# EP2C5T144C8.net
KiCad netlist of a schematic drawn in Altium Designer
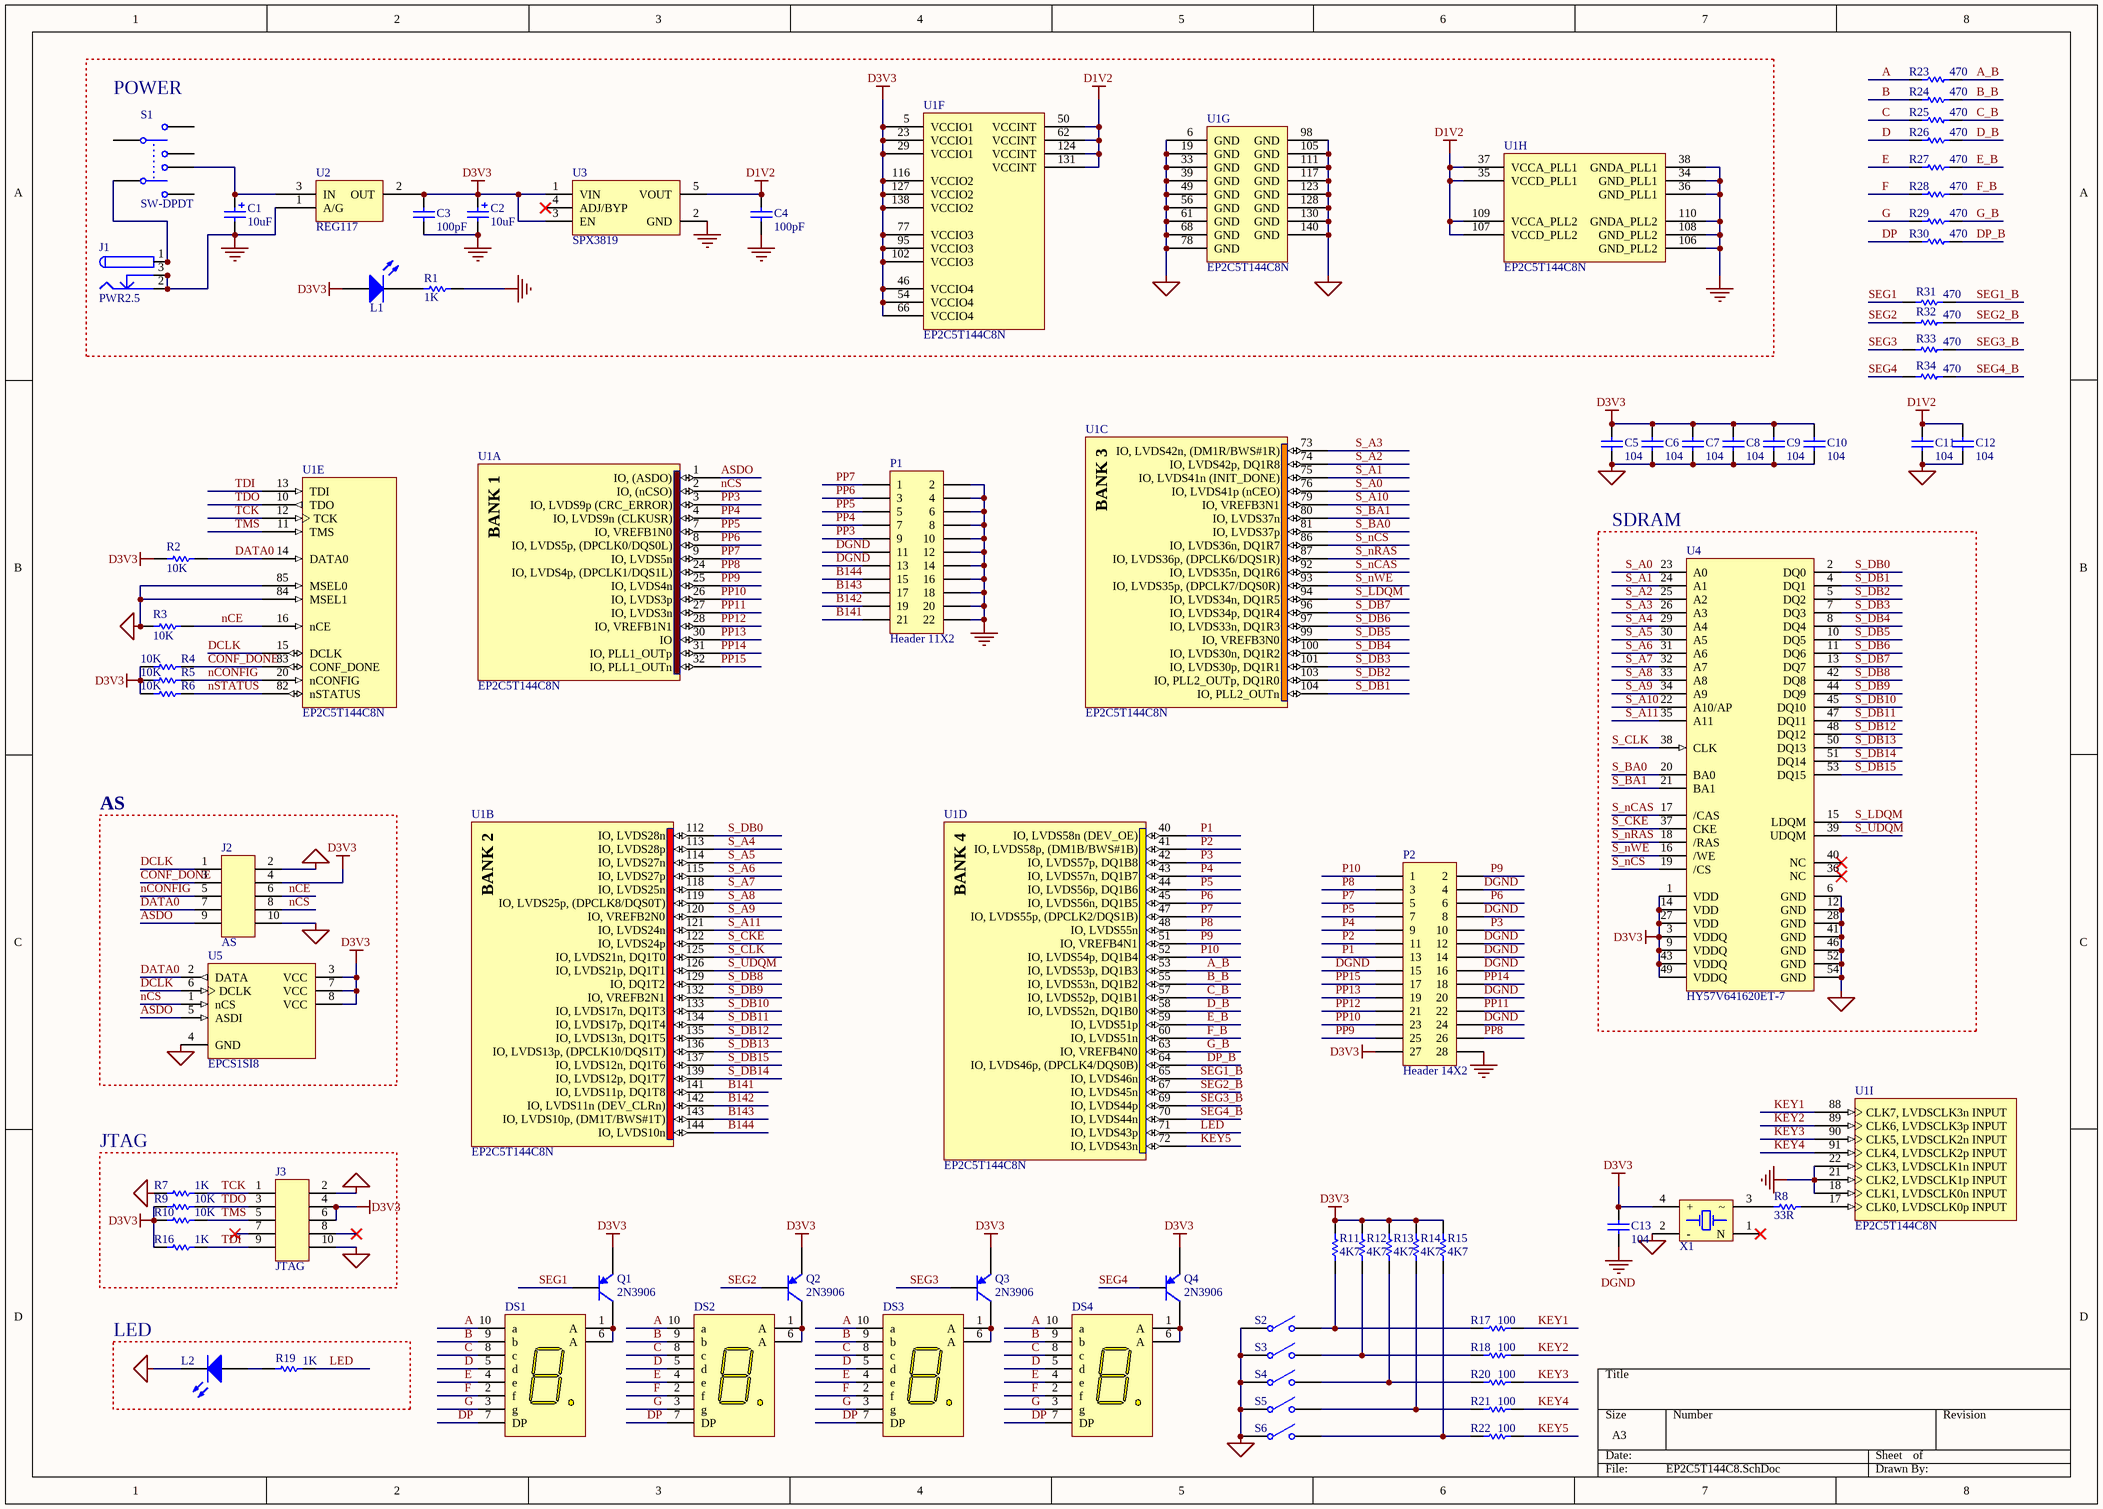
[diagram p0: EP2C5T144C8.SchDoc]

(export (version "E")
  (design (tool "Eeschema 10.0.6"))
  (components
    (comp (ref "C1")
      (value "10uF")
      (footprint "tanCap")
      (description "Polarized Capacitor (Surface Mount)")
      (fields (field (name "Comment") "Cap Pol3") (field (name "PUBLISHER") "Altium Limited"))
      (libsource (lib "Miscellaneous Devices") (part "Cap Pol3"))
    )
    (comp (ref "C2")
      (value "10uF")
      (footprint "tanCap")
      (description "Polarized Capacitor (Surface Mount)")
      (fields (field (name "Comment") "Cap Pol3") (field (name "PUBLISHER") "Altium Limited"))
      (libsource (lib "Miscellaneous Devices") (part "Cap Pol3"))
    )
    (comp (ref "C3")
      (value "100pF")
      (footprint "CC2012-0805")
      (description "Capacitor (Semiconductor SIM Model)")
      (fields (field (name "Comment") "Cap Semi") (field (name "PUBLISHER") "Altium Limited"))
      (libsource (lib "Miscellaneous Devices") (part "Cap Semi"))
    )
    (comp (ref "C4")
      (value "100pF")
      (footprint "CC2012-0805")
      (description "Capacitor (Semiconductor SIM Model)")
      (fields (field (name "Comment") "Cap Semi") (field (name "PUBLISHER") "Altium Limited"))
      (libsource (lib "Miscellaneous Devices") (part "Cap Semi"))
    )
    (comp (ref "C5")
      (value "104")
      (footprint "CC2012-0805")
      (description "Capacitor (Semiconductor SIM Model)")
      (fields (field (name "Comment") "Cap Semi") (field (name "PUBLISHER") "Altium Limited"))
      (libsource (lib "Miscellaneous Devices") (part "Cap Semi"))
    )
    (comp (ref "C6")
      (value "104")
      (footprint "CC2012-0805")
      (description "Capacitor (Semiconductor SIM Model)")
      (fields (field (name "Comment") "Cap Semi") (field (name "PUBLISHER") "Altium Limited"))
      (libsource (lib "Miscellaneous Devices") (part "Cap Semi"))
    )
    (comp (ref "C7")
      (value "104")
      (footprint "CC2012-0805")
      (description "Capacitor (Semiconductor SIM Model)")
      (fields (field (name "Comment") "Cap Semi") (field (name "PUBLISHER") "Altium Limited"))
      (libsource (lib "Miscellaneous Devices") (part "Cap Semi"))
    )
    (comp (ref "C8")
      (value "104")
      (footprint "CC2012-0805")
      (description "Capacitor (Semiconductor SIM Model)")
      (fields (field (name "Comment") "Cap Semi") (field (name "PUBLISHER") "Altium Limited"))
      (libsource (lib "Miscellaneous Devices") (part "Cap Semi"))
    )
    (comp (ref "C9")
      (value "104")
      (footprint "CC2012-0805")
      (description "Capacitor (Semiconductor SIM Model)")
      (fields (field (name "Comment") "Cap Semi") (field (name "PUBLISHER") "Altium Limited"))
      (libsource (lib "Miscellaneous Devices") (part "Cap Semi"))
    )
    (comp (ref "C10")
      (value "104")
      (footprint "CC2012-0805")
      (description "Capacitor (Semiconductor SIM Model)")
      (fields (field (name "Comment") "Cap Semi") (field (name "PUBLISHER") "Altium Limited"))
      (libsource (lib "Miscellaneous Devices") (part "Cap Semi"))
    )
    (comp (ref "C11")
      (value "104")
      (footprint "CC2012-0805")
      (description "Capacitor (Semiconductor SIM Model)")
      (fields (field (name "Comment") "Cap Semi") (field (name "PUBLISHER") "Altium Limited"))
      (libsource (lib "Miscellaneous Devices") (part "Cap Semi"))
    )
    (comp (ref "C12")
      (value "104")
      (footprint "CC2012-0805")
      (description "Capacitor (Semiconductor SIM Model)")
      (fields (field (name "Comment") "Cap Semi") (field (name "PUBLISHER") "Altium Limited"))
      (libsource (lib "Miscellaneous Devices") (part "Cap Semi"))
    )
    (comp (ref "C13")
      (value "104")
      (footprint "CC2012-0805")
      (description "Capacitor")
      (fields (field (name "Comment") "Cap") (field (name "PUBLISHER") "Altium Limited"))
      (libsource (lib "Miscellaneous Devices") (part "Cap"))
    )
    (comp (ref "DS1")
      (value "Dpy Yellow-CA")
      (footprint "LEDDIP-10")
      (description "7.6 mm Micro Bright Yellow 7-Segment Display: CA, RH DP")
      (fields (field (name "PUBLISHER") "Altium Limited"))
      (libsource (lib "Miscellaneous Devices") (part "Dpy Yellow-CA"))
    )
    (comp (ref "DS2")
      (value "Dpy Yellow-CA")
      (footprint "LEDDIP-10")
      (description "7.6 mm Micro Bright Yellow 7-Segment Display: CA, RH DP")
      (fields (field (name "PUBLISHER") "Altium Limited"))
      (libsource (lib "Miscellaneous Devices") (part "Dpy Yellow-CA"))
    )
    (comp (ref "DS3")
      (value "Dpy Yellow-CA")
      (footprint "LEDDIP-10")
      (description "7.6 mm Micro Bright Yellow 7-Segment Display: CA, RH DP")
      (fields (field (name "PUBLISHER") "Altium Limited"))
      (libsource (lib "Miscellaneous Devices") (part "Dpy Yellow-CA"))
    )
    (comp (ref "DS4")
      (value "Dpy Yellow-CA")
      (footprint "LEDDIP-10")
      (description "7.6 mm Micro Bright Yellow 7-Segment Display: CA, RH DP")
      (fields (field (name "PUBLISHER") "Altium Limited"))
      (libsource (lib "Miscellaneous Devices") (part "Dpy Yellow-CA"))
    )
    (comp (ref "J1")
      (value "PWR2.5")
      (footprint "KLD-0202")
      (description "Low Voltage Power Supply Connector")
      (fields (field (name "PUBLISHER") "Altium Limited"))
      (libsource (lib "Miscellaneous Connectors") (part "PWR2.5"))
    )
    (comp (ref "J2") (value "AS") (footprint "JATG_XU") (libsource (lib "myschlib") (part "JTAG_XU")))
    (comp (ref "J3") (value "JTAG") (footprint "JATG_XU") (libsource (lib "myschlib") (part "JTAG_XU")))
    (comp (ref "L1")
      (value "LED-3MM")
      (footprint "CC2012-0805")
      (libsource (lib "SXF'S LIB") (part "LED-3MM"))
    )
    (comp (ref "L2")
      (value "LED-3MM")
      (footprint "CC2012-0805")
      (libsource (lib "SXF'S LIB") (part "LED-3MM"))
    )
    (comp (ref "P1")
      (value "Header 11X2")
      (footprint "HDR2X11")
      (description "Header, 11-Pin, Dual row")
      (fields (field (name "PUBLISHER") "Altium Limited"))
      (libsource (lib "Miscellaneous Connectors") (part "Header 11X2"))
    )
    (comp (ref "P2")
      (value "Header 14X2")
      (footprint "HDR2X14")
      (description "Header, 14-Pin, Dual row")
      (fields (field (name "PUBLISHER") "Altium Limited"))
      (libsource (lib "Miscellaneous Connectors") (part "Header 14X2"))
    )
    (comp (ref "Q1")
      (value "2N3906")
      (footprint "MYLIB:SOT-23")
      (description "PNP General Purpose Amplifier")
      (fields (field (name "PUBLISHER") "Altium Limited"))
      (libsource (lib "Miscellaneous Devices") (part "2N3906"))
    )
    (comp (ref "Q2")
      (value "2N3906")
      (footprint "MYLIB:SOT-23")
      (description "PNP General Purpose Amplifier")
      (fields (field (name "PUBLISHER") "Altium Limited"))
      (libsource (lib "Miscellaneous Devices") (part "2N3906"))
    )
    (comp (ref "Q3")
      (value "2N3906")
      (footprint "MYLIB:SOT-23")
      (description "PNP General Purpose Amplifier")
      (fields (field (name "PUBLISHER") "Altium Limited"))
      (libsource (lib "Miscellaneous Devices") (part "2N3906"))
    )
    (comp (ref "Q4")
      (value "2N3906")
      (footprint "MYLIB:SOT-23")
      (description "PNP General Purpose Amplifier")
      (fields (field (name "PUBLISHER") "Altium Limited"))
      (libsource (lib "Miscellaneous Devices") (part "2N3906"))
    )
    (comp (ref "R1")
      (value "1K")
      (footprint "CR2012-0805")
      (description "Resistor")
      (fields (field (name "Comment") "Res1") (field (name "PUBLISHER") "Altium Limited"))
      (libsource (lib "Miscellaneous Devices") (part "Res1"))
    )
    (comp (ref "R2")
      (value "10K")
      (footprint "MYLIB:CR2012-0805")
      (description "Semiconductor Resistor")
      (fields (field (name "Comment") "Res Semi") (field (name "PUBLISHER") "Altium Limited"))
      (libsource (lib "Miscellaneous Devices") (part "Res Semi"))
    )
    (comp (ref "R3")
      (value "10K")
      (footprint "CR2012-0805")
      (description "Resistor")
      (fields (field (name "Comment") "Res1") (field (name "PUBLISHER") "Altium Limited"))
      (libsource (lib "Miscellaneous Devices") (part "Res1"))
    )
    (comp (ref "R4")
      (value "10K")
      (footprint "CR2012-0805")
      (description "Resistor")
      (fields (field (name "Comment") "Res1") (field (name "PUBLISHER") "Altium Limited"))
      (libsource (lib "Miscellaneous Devices") (part "Res1"))
    )
    (comp (ref "R5")
      (value "10K")
      (footprint "CR2012-0805")
      (description "Resistor")
      (fields (field (name "Comment") "Res1") (field (name "PUBLISHER") "Altium Limited"))
      (libsource (lib "Miscellaneous Devices") (part "Res1"))
    )
    (comp (ref "R6")
      (value "10K")
      (footprint "CR2012-0805")
      (description "Resistor")
      (fields (field (name "Comment") "Res1") (field (name "PUBLISHER") "Altium Limited"))
      (libsource (lib "Miscellaneous Devices") (part "Res1"))
    )
    (comp (ref "R7")
      (value "1K")
      (footprint "CR2012-0805")
      (description "Resistor")
      (fields (field (name "Comment") "Res1") (field (name "PUBLISHER") "Altium Limited"))
      (libsource (lib "Miscellaneous Devices") (part "Res1"))
    )
    (comp (ref "R8")
      (value "33R")
      (footprint "CR2012-0805")
      (description "Resistor")
      (fields (field (name "Comment") "Res1") (field (name "PUBLISHER") "Altium Limited"))
      (libsource (lib "Miscellaneous Devices") (part "Res1"))
    )
    (comp (ref "R9")
      (value "10K")
      (footprint "CR2012-0805")
      (description "Resistor")
      (fields (field (name "Comment") "Res1") (field (name "PUBLISHER") "Altium Limited"))
      (libsource (lib "Miscellaneous Devices") (part "Res1"))
    )
    (comp (ref "R10")
      (value "10K")
      (footprint "CR2012-0805")
      (description "Resistor")
      (fields (field (name "Comment") "Res1") (field (name "PUBLISHER") "Altium Limited"))
      (libsource (lib "Miscellaneous Devices") (part "Res1"))
    )
    (comp (ref "R11")
      (value "4K7")
      (footprint "CR2012-0805")
      (description "Resistor")
      (fields (field (name "Comment") "Res1") (field (name "PUBLISHER") "Altium Limited"))
      (libsource (lib "Miscellaneous Devices") (part "Res1"))
    )
    (comp (ref "R12")
      (value "4K7")
      (footprint "CR2012-0805")
      (description "Resistor")
      (fields (field (name "Comment") "Res1") (field (name "PUBLISHER") "Altium Limited"))
      (libsource (lib "Miscellaneous Devices") (part "Res1"))
    )
    (comp (ref "R13")
      (value "4K7")
      (footprint "CR2012-0805")
      (description "Resistor")
      (fields (field (name "Comment") "Res1") (field (name "PUBLISHER") "Altium Limited"))
      (libsource (lib "Miscellaneous Devices") (part "Res1"))
    )
    (comp (ref "R14")
      (value "4K7")
      (footprint "CR2012-0805")
      (description "Resistor")
      (fields (field (name "Comment") "Res1") (field (name "PUBLISHER") "Altium Limited"))
      (libsource (lib "Miscellaneous Devices") (part "Res1"))
    )
    (comp (ref "R15")
      (value "4K7")
      (footprint "CR2012-0805")
      (description "Resistor")
      (fields (field (name "Comment") "Res1") (field (name "PUBLISHER") "Altium Limited"))
      (libsource (lib "Miscellaneous Devices") (part "Res1"))
    )
    (comp (ref "R16")
      (value "1K")
      (footprint "CR2012-0805")
      (description "Resistor")
      (fields (field (name "Comment") "Res1") (field (name "PUBLISHER") "Altium Limited"))
      (libsource (lib "Miscellaneous Devices") (part "Res1"))
    )
    (comp (ref "R17")
      (value "100")
      (footprint "CR2012-0805")
      (description "Resistor")
      (fields (field (name "Comment") "Res1") (field (name "PUBLISHER") "Altium Limited"))
      (libsource (lib "Miscellaneous Devices") (part "Res1"))
    )
    (comp (ref "R18")
      (value "100")
      (footprint "CR2012-0805")
      (description "Resistor")
      (fields (field (name "Comment") "Res1") (field (name "PUBLISHER") "Altium Limited"))
      (libsource (lib "Miscellaneous Devices") (part "Res1"))
    )
    (comp (ref "R19")
      (value "1K")
      (footprint "CR2012-0805")
      (description "Resistor")
      (fields (field (name "Comment") "Res1") (field (name "PUBLISHER") "Altium Limited"))
      (libsource (lib "Miscellaneous Devices") (part "Res1"))
    )
    (comp (ref "R20")
      (value "100")
      (footprint "CR2012-0805")
      (description "Resistor")
      (fields (field (name "Comment") "Res1") (field (name "PUBLISHER") "Altium Limited"))
      (libsource (lib "Miscellaneous Devices") (part "Res1"))
    )
    (comp (ref "R21")
      (value "100")
      (footprint "CR2012-0805")
      (description "Resistor")
      (fields (field (name "Comment") "Res1") (field (name "PUBLISHER") "Altium Limited"))
      (libsource (lib "Miscellaneous Devices") (part "Res1"))
    )
    (comp (ref "R22")
      (value "100")
      (footprint "CR2012-0805")
      (description "Resistor")
      (fields (field (name "Comment") "Res1") (field (name "PUBLISHER") "Altium Limited"))
      (libsource (lib "Miscellaneous Devices") (part "Res1"))
    )
    (comp (ref "R23")
      (value "470")
      (footprint "CR2012-0805")
      (description "Resistor")
      (fields (field (name "Comment") "Res1") (field (name "PUBLISHER") "Altium Limited"))
      (libsource (lib "Miscellaneous Devices") (part "Res1"))
    )
    (comp (ref "R24")
      (value "470")
      (footprint "CR2012-0805")
      (description "Resistor")
      (fields (field (name "Comment") "Res1") (field (name "PUBLISHER") "Altium Limited"))
      (libsource (lib "Miscellaneous Devices") (part "Res1"))
    )
    (comp (ref "R25")
      (value "470")
      (footprint "CR2012-0805")
      (description "Resistor")
      (fields (field (name "Comment") "Res1") (field (name "PUBLISHER") "Altium Limited"))
      (libsource (lib "Miscellaneous Devices") (part "Res1"))
    )
    (comp (ref "R26")
      (value "470")
      (footprint "CR2012-0805")
      (description "Resistor")
      (fields (field (name "Comment") "Res1") (field (name "PUBLISHER") "Altium Limited"))
      (libsource (lib "Miscellaneous Devices") (part "Res1"))
    )
    (comp (ref "R27")
      (value "470")
      (footprint "CR2012-0805")
      (description "Resistor")
      (fields (field (name "Comment") "Res1") (field (name "PUBLISHER") "Altium Limited"))
      (libsource (lib "Miscellaneous Devices") (part "Res1"))
    )
    (comp (ref "R28")
      (value "470")
      (footprint "CR2012-0805")
      (description "Resistor")
      (fields (field (name "Comment") "Res1") (field (name "PUBLISHER") "Altium Limited"))
      (libsource (lib "Miscellaneous Devices") (part "Res1"))
    )
    (comp (ref "R29")
      (value "470")
      (footprint "CR2012-0805")
      (description "Resistor")
      (fields (field (name "Comment") "Res1") (field (name "PUBLISHER") "Altium Limited"))
      (libsource (lib "Miscellaneous Devices") (part "Res1"))
    )
    (comp (ref "R30")
      (value "470")
      (footprint "CR2012-0805")
      (description "Resistor")
      (fields (field (name "Comment") "Res1") (field (name "PUBLISHER") "Altium Limited"))
      (libsource (lib "Miscellaneous Devices") (part "Res1"))
    )
    (comp (ref "R31")
      (value "470")
      (footprint "CR2012-0805")
      (description "Resistor")
      (fields (field (name "Comment") "Res1") (field (name "PUBLISHER") "Altium Limited"))
      (libsource (lib "Miscellaneous Devices") (part "Res1"))
    )
    (comp (ref "R32")
      (value "470")
      (footprint "CR2012-0805")
      (description "Resistor")
      (fields (field (name "Comment") "Res1") (field (name "PUBLISHER") "Altium Limited"))
      (libsource (lib "Miscellaneous Devices") (part "Res1"))
    )
    (comp (ref "R33")
      (value "470")
      (footprint "CR2012-0805")
      (description "Resistor")
      (fields (field (name "Comment") "Res1") (field (name "PUBLISHER") "Altium Limited"))
      (libsource (lib "Miscellaneous Devices") (part "Res1"))
    )
    (comp (ref "R34")
      (value "470")
      (footprint "CR2012-0805")
      (description "Resistor")
      (fields (field (name "Comment") "Res1") (field (name "PUBLISHER") "Altium Limited"))
      (libsource (lib "Miscellaneous Devices") (part "Res1"))
    )
    (comp (ref "S1")
      (value "SW-DPDT")
      (footprint "DPDT-6")
      (description "Double-Pole, Double-Throw Switch")
      (fields (field (name "PUBLISHER") "Altium Limited"))
      (libsource (lib "Miscellaneous Devices") (part "SW-DPDT"))
    )
    (comp (ref "S2")
      (value "SW-SPST")
      (footprint "MYLIB:SW2")
      (description "Single-Pole, Single-Throw Switch")
      (fields (field (name "PUBLISHER") "Altium Limited"))
      (libsource (lib "Miscellaneous Devices") (part "SW-SPST"))
    )
    (comp (ref "S3")
      (value "SW-SPST")
      (footprint "MYLIB:SW2")
      (description "Single-Pole, Single-Throw Switch")
      (fields (field (name "PUBLISHER") "Altium Limited"))
      (libsource (lib "Miscellaneous Devices") (part "SW-SPST"))
    )
    (comp (ref "S4")
      (value "SW-SPST")
      (footprint "MYLIB:SW2")
      (description "Single-Pole, Single-Throw Switch")
      (fields (field (name "PUBLISHER") "Altium Limited"))
      (libsource (lib "Miscellaneous Devices") (part "SW-SPST"))
    )
    (comp (ref "S5")
      (value "SW-SPST")
      (footprint "MYLIB:SW2")
      (description "Single-Pole, Single-Throw Switch")
      (fields (field (name "PUBLISHER") "Altium Limited"))
      (libsource (lib "Miscellaneous Devices") (part "SW-SPST"))
    )
    (comp (ref "S6")
      (value "SW-SPST")
      (footprint "MYLIB:SW2")
      (description "Single-Pole, Single-Throw Switch")
      (fields (field (name "PUBLISHER") "Altium Limited"))
      (libsource (lib "Miscellaneous Devices") (part "SW-SPST"))
    )
    (comp (ref "U1")
      (value "EP2C5T144C8N")
      (footprint "TQFP144_N")
      (fields (field (name "PUBLISHER") "Altium Limited"))
      (libsource (lib "Altera Cyclone II") (part "EP2C5T144C8N"))
    )
    (comp (ref "U2")
      (value "REG117")
      (footprint "MYLIB:SOT223")
      (libsource (lib "SXF'S LIB") (part "REG117"))
    )
    (comp (ref "U3") (value "SPX3819") (footprint "SO-G5/P.95") (libsource (lib "myschlib") (part "SPX3819")))
    (comp (ref "U4")
      (value "HY57V641620ET-7")
      (footprint "TSOP-54")
      (libsource (lib "myschlib") (part "HY57V641620ET-7"))
    )
    (comp (ref "U5")
      (value "EPCS1SI8")
      (footprint "MYLIB:SOIC8")
      (fields (field (name "PUBLISHER") "Altium Limited"))
      (libsource (lib "Altera EPCS Configuration Device") (part "EPCS1SI8"))
    )
    (comp (ref "X1")
      (value "XTAL-S")
      (footprint "MYLIB:DSO-N4")
      (libsource (lib "SXF'S LIB") (part "XTAL-S"))
    )
  )
  (nets
    (net (code "1") (name "/A") (class "Default")
      (node (ref "DS1") (pin "10") (pinfunction "a_10") (pintype "passive"))
      (node (ref "DS2") (pin "10") (pinfunction "a_10") (pintype "passive"))
      (node (ref "DS3") (pin "10") (pinfunction "a_10") (pintype "passive"))
      (node (ref "DS4") (pin "10") (pinfunction "a_10") (pintype "passive"))
      (node (ref "R23") (pin "2") (pinfunction "2_2") (pintype "passive"))
    )
    (net (code "2") (name "/ASDO") (class "Default")
      (node (ref "J2") (pin "9") (pinfunction "9_9") (pintype "passive"))
      (node (ref "U1") (pin "1") (pinfunction "IO,_(ASDO)_1") (pintype "bidirectional"))
      (node (ref "U5") (pin "5") (pinfunction "ASDI_5") (pintype "input"))
    )
    (net (code "3") (name "/A_B") (class "Default")
      (node (ref "R23") (pin "1") (pinfunction "1_1") (pintype "passive"))
      (node (ref "U1") (pin "53") (pinfunction "IO,_LVDS53p,_DQ1B3_53") (pintype "bidirectional"))
    )
    (net (code "4") (name "/B") (class "Default")
      (node (ref "DS1") (pin "9") (pinfunction "b_9") (pintype "passive"))
      (node (ref "DS2") (pin "9") (pinfunction "b_9") (pintype "passive"))
      (node (ref "DS3") (pin "9") (pinfunction "b_9") (pintype "passive"))
      (node (ref "DS4") (pin "9") (pinfunction "b_9") (pintype "passive"))
      (node (ref "R24") (pin "2") (pinfunction "2_2") (pintype "passive"))
    )
    (net (code "5") (name "/B141") (class "Default")
      (node (ref "P1") (pin "21") (pinfunction "21_21") (pintype "passive"))
      (node (ref "U1") (pin "141") (pinfunction "IO,_LVDS11p,_DQ1T8_141") (pintype "bidirectional"))
    )
    (net (code "6") (name "/B142") (class "Default")
      (node (ref "P1") (pin "19") (pinfunction "19_19") (pintype "passive"))
      (node (ref "U1") (pin "142") (pinfunction "IO,_LVDS11n_(DEV_CLRn)_142") (pintype "bidirectional"))
    )
    (net (code "7") (name "/B143") (class "Default")
      (node (ref "P1") (pin "17") (pinfunction "17_17") (pintype "passive"))
      (node (ref "U1") (pin "143") (pinfunction "IO,_LVDS10p,_(DM1T/BWS#1T)_143") (pintype "bidirectional"))
    )
    (net (code "8") (name "/B144") (class "Default")
      (node (ref "P1") (pin "15") (pinfunction "15_15") (pintype "passive"))
      (node (ref "U1") (pin "144") (pinfunction "IO,_LVDS10n_144") (pintype "bidirectional"))
    )
    (net (code "9") (name "/B_B") (class "Default")
      (node (ref "R24") (pin "1") (pinfunction "1_1") (pintype "passive"))
      (node (ref "U1") (pin "55") (pinfunction "IO,_LVDS53n,_DQ1B2_55") (pintype "bidirectional"))
    )
    (net (code "10") (name "/C") (class "Default")
      (node (ref "DS1") (pin "8") (pinfunction "c_8") (pintype "passive"))
      (node (ref "DS2") (pin "8") (pinfunction "c_8") (pintype "passive"))
      (node (ref "DS3") (pin "8") (pinfunction "c_8") (pintype "passive"))
      (node (ref "DS4") (pin "8") (pinfunction "c_8") (pintype "passive"))
      (node (ref "R25") (pin "2") (pinfunction "2_2") (pintype "passive"))
    )
    (net (code "11") (name "/CONF_DONE") (class "Default")
      (node (ref "J2") (pin "3") (pinfunction "3_3") (pintype "passive"))
      (node (ref "R4") (pin "1") (pinfunction "1_1") (pintype "passive"))
      (node (ref "U1") (pin "83") (pinfunction "CONF_DONE_83") (pintype "bidirectional"))
    )
    (net (code "12") (name "/C_B") (class "Default")
      (node (ref "R25") (pin "1") (pinfunction "1_1") (pintype "passive"))
      (node (ref "U1") (pin "57") (pinfunction "IO,_LVDS52p,_DQ1B1_57") (pintype "bidirectional"))
    )
    (net (code "13") (name "/D") (class "Default")
      (node (ref "DS1") (pin "5") (pinfunction "d_5") (pintype "passive"))
      (node (ref "DS2") (pin "5") (pinfunction "d_5") (pintype "passive"))
      (node (ref "DS3") (pin "5") (pinfunction "d_5") (pintype "passive"))
      (node (ref "DS4") (pin "5") (pinfunction "d_5") (pintype "passive"))
      (node (ref "R26") (pin "2") (pinfunction "2_2") (pintype "passive"))
    )
    (net (code "14") (name "/DATA0") (class "Default")
      (node (ref "J2") (pin "7") (pinfunction "7_7") (pintype "passive"))
      (node (ref "R2") (pin "1") (pinfunction "1_1") (pintype "passive"))
      (node (ref "U1") (pin "14") (pinfunction "DATA0_14") (pintype "input"))
      (node (ref "U5") (pin "2") (pinfunction "DATA_2") (pintype "output"))
    )
    (net (code "15") (name "/DCLK") (class "Default")
      (node (ref "J2") (pin "1") (pinfunction "1_1") (pintype "passive"))
      (node (ref "U1") (pin "15") (pinfunction "DCLK_15") (pintype "bidirectional"))
      (node (ref "U5") (pin "6") (pinfunction "DCLK_6") (pintype "input"))
    )
    (net (code "16") (name "/DP") (class "Default")
      (node (ref "DS1") (pin "7") (pinfunction "DP_7") (pintype "passive"))
      (node (ref "DS2") (pin "7") (pinfunction "DP_7") (pintype "passive"))
      (node (ref "DS3") (pin "7") (pinfunction "DP_7") (pintype "passive"))
      (node (ref "DS4") (pin "7") (pinfunction "DP_7") (pintype "passive"))
      (node (ref "R30") (pin "2") (pinfunction "2_2") (pintype "passive"))
    )
    (net (code "17") (name "/DP_B") (class "Default")
      (node (ref "R30") (pin "1") (pinfunction "1_1") (pintype "passive"))
      (node (ref "U1") (pin "64") (pinfunction "IO,_LVDS46p,_(DPCLK4/DQS0B)_64") (pintype "bidirectional"))
    )
    (net (code "18") (name "/D_B") (class "Default")
      (node (ref "R26") (pin "1") (pinfunction "1_1") (pintype "passive"))
      (node (ref "U1") (pin "58") (pinfunction "IO,_LVDS52n,_DQ1B0_58") (pintype "bidirectional"))
    )
    (net (code "19") (name "/E") (class "Default")
      (node (ref "DS1") (pin "4") (pinfunction "e_4") (pintype "passive"))
      (node (ref "DS2") (pin "4") (pinfunction "e_4") (pintype "passive"))
      (node (ref "DS3") (pin "4") (pinfunction "e_4") (pintype "passive"))
      (node (ref "DS4") (pin "4") (pinfunction "e_4") (pintype "passive"))
      (node (ref "R27") (pin "2") (pinfunction "2_2") (pintype "passive"))
    )
    (net (code "20") (name "/E_B") (class "Default")
      (node (ref "R27") (pin "1") (pinfunction "1_1") (pintype "passive"))
      (node (ref "U1") (pin "59") (pinfunction "IO,_LVDS51p_59") (pintype "bidirectional"))
    )
    (net (code "21") (name "/F") (class "Default")
      (node (ref "DS1") (pin "2") (pinfunction "f_2") (pintype "passive"))
      (node (ref "DS2") (pin "2") (pinfunction "f_2") (pintype "passive"))
      (node (ref "DS3") (pin "2") (pinfunction "f_2") (pintype "passive"))
      (node (ref "DS4") (pin "2") (pinfunction "f_2") (pintype "passive"))
      (node (ref "R28") (pin "2") (pinfunction "2_2") (pintype "passive"))
    )
    (net (code "22") (name "/F_B") (class "Default")
      (node (ref "R28") (pin "1") (pinfunction "1_1") (pintype "passive"))
      (node (ref "U1") (pin "60") (pinfunction "IO,_LVDS51n_60") (pintype "bidirectional"))
    )
    (net (code "23") (name "/G") (class "Default")
      (node (ref "DS1") (pin "3") (pinfunction "g_3") (pintype "passive"))
      (node (ref "DS2") (pin "3") (pinfunction "g_3") (pintype "passive"))
      (node (ref "DS3") (pin "3") (pinfunction "g_3") (pintype "passive"))
      (node (ref "DS4") (pin "3") (pinfunction "g_3") (pintype "passive"))
      (node (ref "R29") (pin "2") (pinfunction "2_2") (pintype "passive"))
    )
    (net (code "24") (name "/G_B") (class "Default")
      (node (ref "R29") (pin "1") (pinfunction "1_1") (pintype "passive"))
      (node (ref "U1") (pin "63") (pinfunction "IO,_VREFB4N0_63") (pintype "bidirectional"))
    )
    (net (code "25") (name "/KEY1") (class "Default")
      (node (ref "R17") (pin "1") (pinfunction "1_1") (pintype "passive"))
      (node (ref "U1") (pin "88") (pinfunction "CLK7,_LVDSCLK3n_INPUT_88") (pintype "input"))
    )
    (net (code "26") (name "/KEY2") (class "Default")
      (node (ref "R18") (pin "1") (pinfunction "1_1") (pintype "passive"))
      (node (ref "U1") (pin "89") (pinfunction "CLK6,_LVDSCLK3p_INPUT_89") (pintype "input"))
    )
    (net (code "27") (name "/KEY3") (class "Default")
      (node (ref "R20") (pin "1") (pinfunction "1_1") (pintype "passive"))
      (node (ref "U1") (pin "90") (pinfunction "CLK5,_LVDSCLK2n_INPUT_90") (pintype "input"))
    )
    (net (code "28") (name "/KEY4") (class "Default")
      (node (ref "R21") (pin "1") (pinfunction "1_1") (pintype "passive"))
      (node (ref "U1") (pin "91") (pinfunction "CLK4,_LVDSCLK2p_INPUT_91") (pintype "input"))
    )
    (net (code "29") (name "/KEY5") (class "Default")
      (node (ref "R22") (pin "1") (pinfunction "1_1") (pintype "passive"))
      (node (ref "U1") (pin "72") (pinfunction "IO,_LVDS43n_72") (pintype "bidirectional"))
    )
    (net (code "30") (name "/LED") (class "Default")
      (node (ref "R19") (pin "1") (pinfunction "1_1") (pintype "passive"))
      (node (ref "U1") (pin "71") (pinfunction "IO,_LVDS43p_71") (pintype "bidirectional"))
    )
    (net (code "31") (name "/P1") (class "Default")
      (node (ref "P2") (pin "13") (pinfunction "13_13") (pintype "passive"))
      (node (ref "U1") (pin "40") (pinfunction "IO,_LVDS58n_(DEV_OE)_40") (pintype "bidirectional"))
    )
    (net (code "32") (name "/P2") (class "Default")
      (node (ref "P2") (pin "11") (pinfunction "11_11") (pintype "passive"))
      (node (ref "U1") (pin "41") (pinfunction "IO,_LVDS58p,_(DM1B/BWS#1B)_41") (pintype "bidirectional"))
    )
    (net (code "33") (name "/P3") (class "Default")
      (node (ref "P2") (pin "10") (pinfunction "10_10") (pintype "passive"))
      (node (ref "U1") (pin "42") (pinfunction "IO,_LVDS57p,_DQ1B8_42") (pintype "bidirectional"))
    )
    (net (code "34") (name "/P4") (class "Default")
      (node (ref "P2") (pin "9") (pinfunction "9_9") (pintype "passive"))
      (node (ref "U1") (pin "43") (pinfunction "IO,_LVDS57n,_DQ1B7_43") (pintype "bidirectional"))
    )
    (net (code "35") (name "/P5") (class "Default")
      (node (ref "P2") (pin "7") (pinfunction "7_7") (pintype "passive"))
      (node (ref "U1") (pin "44") (pinfunction "IO,_LVDS56p,_DQ1B6_44") (pintype "bidirectional"))
    )
    (net (code "36") (name "/P6") (class "Default")
      (node (ref "P2") (pin "6") (pinfunction "6_6") (pintype "passive"))
      (node (ref "U1") (pin "45") (pinfunction "IO,_LVDS56n,_DQ1B5_45") (pintype "bidirectional"))
    )
    (net (code "37") (name "/P7") (class "Default")
      (node (ref "P2") (pin "5") (pinfunction "5_5") (pintype "passive"))
      (node (ref "U1") (pin "47") (pinfunction "IO,_LVDS55p,_(DPCLK2/DQS1B)_47") (pintype "bidirectional"))
    )
    (net (code "38") (name "/P8") (class "Default")
      (node (ref "P2") (pin "3") (pinfunction "3_3") (pintype "passive"))
      (node (ref "U1") (pin "48") (pinfunction "IO,_LVDS55n_48") (pintype "bidirectional"))
    )
    (net (code "39") (name "/P9") (class "Default")
      (node (ref "P2") (pin "2") (pinfunction "2_2") (pintype "passive"))
      (node (ref "U1") (pin "51") (pinfunction "IO,_VREFB4N1_51") (pintype "bidirectional"))
    )
    (net (code "40") (name "/P10") (class "Default")
      (node (ref "P2") (pin "1") (pinfunction "1_1") (pintype "passive"))
      (node (ref "U1") (pin "52") (pinfunction "IO,_LVDS54p,_DQ1B4_52") (pintype "bidirectional"))
    )
    (net (code "41") (name "/PP3") (class "Default")
      (node (ref "P1") (pin "9") (pinfunction "9_9") (pintype "passive"))
      (node (ref "U1") (pin "3") (pinfunction "IO,_LVDS9p_(CRC_ERROR)_3") (pintype "bidirectional"))
    )
    (net (code "42") (name "/PP4") (class "Default")
      (node (ref "P1") (pin "7") (pinfunction "7_7") (pintype "passive"))
      (node (ref "U1") (pin "4") (pinfunction "IO,_LVDS9n_(CLKUSR)_4") (pintype "bidirectional"))
    )
    (net (code "43") (name "/PP5") (class "Default")
      (node (ref "P1") (pin "5") (pinfunction "5_5") (pintype "passive"))
      (node (ref "U1") (pin "7") (pinfunction "IO,_VREFB1N0_7") (pintype "bidirectional"))
    )
    (net (code "44") (name "/PP6") (class "Default")
      (node (ref "P1") (pin "3") (pinfunction "3_3") (pintype "passive"))
      (node (ref "U1") (pin "8") (pinfunction "IO,_LVDS5p,_(DPCLK0/DQS0L)_8") (pintype "bidirectional"))
    )
    (net (code "45") (name "/PP7") (class "Default")
      (node (ref "P1") (pin "1") (pinfunction "1_1") (pintype "passive"))
      (node (ref "U1") (pin "9") (pinfunction "IO,_LVDS5n_9") (pintype "bidirectional"))
    )
    (net (code "46") (name "/PP8") (class "Default")
      (node (ref "P2") (pin "26") (pinfunction "26_26") (pintype "passive"))
      (node (ref "U1") (pin "24") (pinfunction "IO,_LVDS4p,_(DPCLK1/DQS1L)_24") (pintype "bidirectional"))
    )
    (net (code "47") (name "/PP9") (class "Default")
      (node (ref "P2") (pin "25") (pinfunction "25_25") (pintype "passive"))
      (node (ref "U1") (pin "25") (pinfunction "IO,_LVDS4n_25") (pintype "bidirectional"))
    )
    (net (code "48") (name "/PP10") (class "Default")
      (node (ref "P2") (pin "23") (pinfunction "23_23") (pintype "passive"))
      (node (ref "U1") (pin "26") (pinfunction "IO,_LVDS3p_26") (pintype "bidirectional"))
    )
    (net (code "49") (name "/PP11") (class "Default")
      (node (ref "P2") (pin "22") (pinfunction "22_22") (pintype "passive"))
      (node (ref "U1") (pin "27") (pinfunction "IO,_LVDS3n_27") (pintype "bidirectional"))
    )
    (net (code "50") (name "/PP12") (class "Default")
      (node (ref "P2") (pin "21") (pinfunction "21_21") (pintype "passive"))
      (node (ref "U1") (pin "28") (pinfunction "IO,_VREFB1N1_28") (pintype "bidirectional"))
    )
    (net (code "51") (name "/PP13") (class "Default")
      (node (ref "P2") (pin "19") (pinfunction "19_19") (pintype "passive"))
      (node (ref "U1") (pin "30") (pinfunction "IO_30") (pintype "bidirectional"))
    )
    (net (code "52") (name "/PP14") (class "Default")
      (node (ref "P2") (pin "18") (pinfunction "18_18") (pintype "passive"))
      (node (ref "U1") (pin "31") (pinfunction "IO,_PLL1_OUTp_31") (pintype "bidirectional"))
    )
    (net (code "53") (name "/PP15") (class "Default")
      (node (ref "P2") (pin "17") (pinfunction "17_17") (pintype "passive"))
      (node (ref "U1") (pin "32") (pinfunction "IO,_PLL1_OUTn_32") (pintype "bidirectional"))
    )
    (net (code "54") (name "/SEG1") (class "Default")
      (node (ref "Q1") (pin "2") (pinfunction "B_2") (pintype "passive"))
      (node (ref "R31") (pin "2") (pinfunction "2_2") (pintype "passive"))
    )
    (net (code "55") (name "/SEG1_B") (class "Default")
      (node (ref "R31") (pin "1") (pinfunction "1_1") (pintype "passive"))
      (node (ref "U1") (pin "65") (pinfunction "IO,_LVDS46n_65") (pintype "bidirectional"))
    )
    (net (code "56") (name "/SEG2") (class "Default")
      (node (ref "Q2") (pin "2") (pinfunction "B_2") (pintype "passive"))
      (node (ref "R32") (pin "2") (pinfunction "2_2") (pintype "passive"))
    )
    (net (code "57") (name "/SEG2_B") (class "Default")
      (node (ref "R32") (pin "1") (pinfunction "1_1") (pintype "passive"))
      (node (ref "U1") (pin "67") (pinfunction "IO,_LVDS45n_67") (pintype "bidirectional"))
    )
    (net (code "58") (name "/SEG3") (class "Default")
      (node (ref "Q3") (pin "2") (pinfunction "B_2") (pintype "passive"))
      (node (ref "R33") (pin "2") (pinfunction "2_2") (pintype "passive"))
    )
    (net (code "59") (name "/SEG3_B") (class "Default")
      (node (ref "R33") (pin "1") (pinfunction "1_1") (pintype "passive"))
      (node (ref "U1") (pin "69") (pinfunction "IO,_LVDS44p_69") (pintype "bidirectional"))
    )
    (net (code "60") (name "/SEG4") (class "Default")
      (node (ref "Q4") (pin "2") (pinfunction "B_2") (pintype "passive"))
      (node (ref "R34") (pin "2") (pinfunction "2_2") (pintype "passive"))
    )
    (net (code "61") (name "/SEG4_B") (class "Default")
      (node (ref "R34") (pin "1") (pinfunction "1_1") (pintype "passive"))
      (node (ref "U1") (pin "70") (pinfunction "IO,_LVDS44n_70") (pintype "bidirectional"))
    )
    (net (code "62") (name "/S_A0") (class "Default")
      (node (ref "U1") (pin "76") (pinfunction "IO,_LVDS41p_(nCEO)_76") (pintype "bidirectional"))
      (node (ref "U4") (pin "23") (pinfunction "A0_23") (pintype "passive"))
    )
    (net (code "63") (name "/S_A1") (class "Default")
      (node (ref "U1") (pin "75") (pinfunction "IO,_LVDS41n_(INIT_DONE)_75") (pintype "bidirectional"))
      (node (ref "U4") (pin "24") (pinfunction "A1_24") (pintype "passive"))
    )
    (net (code "64") (name "/S_A2") (class "Default")
      (node (ref "U1") (pin "74") (pinfunction "IO,_LVDS42p,_DQ1R8_74") (pintype "bidirectional"))
      (node (ref "U4") (pin "25") (pinfunction "A2_25") (pintype "passive"))
    )
    (net (code "65") (name "/S_A3") (class "Default")
      (node (ref "U1") (pin "73") (pinfunction "IO,_LVDS42n,_(DM1R/BWS#1R)_73") (pintype "bidirectional"))
      (node (ref "U4") (pin "26") (pinfunction "A3_26") (pintype "passive"))
    )
    (net (code "66") (name "/S_A4") (class "Default")
      (node (ref "U1") (pin "113") (pinfunction "IO,_LVDS28p_113") (pintype "bidirectional"))
      (node (ref "U4") (pin "29") (pinfunction "A4_29") (pintype "passive"))
    )
    (net (code "67") (name "/S_A5") (class "Default")
      (node (ref "U1") (pin "114") (pinfunction "IO,_LVDS27n_114") (pintype "bidirectional"))
      (node (ref "U4") (pin "30") (pinfunction "A5_30") (pintype "passive"))
    )
    (net (code "68") (name "/S_A6") (class "Default")
      (node (ref "U1") (pin "115") (pinfunction "IO,_LVDS27p_115") (pintype "bidirectional"))
      (node (ref "U4") (pin "31") (pinfunction "A6_31") (pintype "passive"))
    )
    (net (code "69") (name "/S_A7") (class "Default")
      (node (ref "U1") (pin "118") (pinfunction "IO,_LVDS25n_118") (pintype "bidirectional"))
      (node (ref "U4") (pin "32") (pinfunction "A7_32") (pintype "passive"))
    )
    (net (code "70") (name "/S_A8") (class "Default")
      (node (ref "U1") (pin "119") (pinfunction "IO,_LVDS25p,_(DPCLK8/DQS0T)_119") (pintype "bidirectional"))
      (node (ref "U4") (pin "33") (pinfunction "A8_33") (pintype "passive"))
    )
    (net (code "71") (name "/S_A9") (class "Default")
      (node (ref "U1") (pin "120") (pinfunction "IO,_VREFB2N0_120") (pintype "bidirectional"))
      (node (ref "U4") (pin "34") (pinfunction "A9_34") (pintype "passive"))
    )
    (net (code "72") (name "/S_A10") (class "Default")
      (node (ref "U1") (pin "79") (pinfunction "IO,_VREFB3N1_79") (pintype "bidirectional"))
      (node (ref "U4") (pin "22") (pinfunction "A10/AP_22") (pintype "passive"))
    )
    (net (code "73") (name "/S_A11") (class "Default")
      (node (ref "U1") (pin "121") (pinfunction "IO,_LVDS24n_121") (pintype "bidirectional"))
      (node (ref "U4") (pin "35") (pinfunction "A11_35") (pintype "passive"))
    )
    (net (code "74") (name "/S_BA0") (class "Default")
      (node (ref "U1") (pin "81") (pinfunction "IO,_LVDS37p_81") (pintype "bidirectional"))
      (node (ref "U4") (pin "20") (pinfunction "BA0_20") (pintype "passive"))
    )
    (net (code "75") (name "/S_BA1") (class "Default")
      (node (ref "U1") (pin "80") (pinfunction "IO,_LVDS37n_80") (pintype "bidirectional"))
      (node (ref "U4") (pin "21") (pinfunction "BA1_21") (pintype "passive"))
    )
    (net (code "76") (name "/S_CKE") (class "Default")
      (node (ref "U1") (pin "122") (pinfunction "IO,_LVDS24p_122") (pintype "bidirectional"))
      (node (ref "U4") (pin "37") (pinfunction "CKE_37") (pintype "passive"))
    )
    (net (code "77") (name "/S_CLK") (class "Default")
      (node (ref "U1") (pin "125") (pinfunction "IO,_LVDS21n,_DQ1T0_125") (pintype "bidirectional"))
      (node (ref "U4") (pin "38") (pinfunction "CLK_38") (pintype "input"))
    )
    (net (code "78") (name "/S_DB0") (class "Default")
      (node (ref "U1") (pin "112") (pinfunction "IO,_LVDS28n_112") (pintype "bidirectional"))
      (node (ref "U4") (pin "2") (pinfunction "DQ0_2") (pintype "passive"))
    )
    (net (code "79") (name "/S_DB1") (class "Default")
      (node (ref "U1") (pin "104") (pinfunction "IO,_PLL2_OUTn_104") (pintype "bidirectional"))
      (node (ref "U4") (pin "4") (pinfunction "DQ1_4") (pintype "passive"))
    )
    (net (code "80") (name "/S_DB2") (class "Default")
      (node (ref "U1") (pin "103") (pinfunction "IO,_PLL2_OUTp,_DQ1R0_103") (pintype "bidirectional"))
      (node (ref "U4") (pin "5") (pinfunction "DQ2_5") (pintype "passive"))
    )
    (net (code "81") (name "/S_DB3") (class "Default")
      (node (ref "U1") (pin "101") (pinfunction "IO,_LVDS30p,_DQ1R1_101") (pintype "bidirectional"))
      (node (ref "U4") (pin "7") (pinfunction "DQ3_7") (pintype "passive"))
    )
    (net (code "82") (name "/S_DB4") (class "Default")
      (node (ref "U1") (pin "100") (pinfunction "IO,_LVDS30n,_DQ1R2_100") (pintype "bidirectional"))
      (node (ref "U4") (pin "8") (pinfunction "DQ4_8") (pintype "passive"))
    )
    (net (code "83") (name "/S_DB5") (class "Default")
      (node (ref "U1") (pin "99") (pinfunction "IO,_VREFB3N0_99") (pintype "bidirectional"))
      (node (ref "U4") (pin "10") (pinfunction "DQ5_10") (pintype "passive"))
    )
    (net (code "84") (name "/S_DB6") (class "Default")
      (node (ref "U1") (pin "97") (pinfunction "IO,_LVDS33n,_DQ1R3_97") (pintype "bidirectional"))
      (node (ref "U4") (pin "11") (pinfunction "DQ6_11") (pintype "passive"))
    )
    (net (code "85") (name "/S_DB7") (class "Default")
      (node (ref "U1") (pin "96") (pinfunction "IO,_LVDS34p,_DQ1R4_96") (pintype "bidirectional"))
      (node (ref "U4") (pin "13") (pinfunction "DQ7_13") (pintype "passive"))
    )
    (net (code "86") (name "/S_DB8") (class "Default")
      (node (ref "U1") (pin "129") (pinfunction "IO,_DQ1T2_129") (pintype "bidirectional"))
      (node (ref "U4") (pin "42") (pinfunction "DQ8_42") (pintype "passive"))
    )
    (net (code "87") (name "/S_DB9") (class "Default")
      (node (ref "U1") (pin "132") (pinfunction "IO,_VREFB2N1_132") (pintype "bidirectional"))
      (node (ref "U4") (pin "44") (pinfunction "DQ9_44") (pintype "passive"))
    )
    (net (code "88") (name "/S_DB10") (class "Default")
      (node (ref "U1") (pin "133") (pinfunction "IO,_LVDS17n,_DQ1T3_133") (pintype "bidirectional"))
      (node (ref "U4") (pin "45") (pinfunction "DQ10_45") (pintype "passive"))
    )
    (net (code "89") (name "/S_DB11") (class "Default")
      (node (ref "U1") (pin "134") (pinfunction "IO,_LVDS17p,_DQ1T4_134") (pintype "bidirectional"))
      (node (ref "U4") (pin "47") (pinfunction "DQ11_47") (pintype "passive"))
    )
    (net (code "90") (name "/S_DB12") (class "Default")
      (node (ref "U1") (pin "135") (pinfunction "IO,_LVDS13n,_DQ1T5_135") (pintype "bidirectional"))
      (node (ref "U4") (pin "48") (pinfunction "DQ12_48") (pintype "passive"))
    )
    (net (code "91") (name "/S_DB13") (class "Default")
      (node (ref "U1") (pin "136") (pinfunction "IO,_LVDS13p,_(DPCLK10/DQS1T)_136") (pintype "bidirectional"))
      (node (ref "U4") (pin "50") (pinfunction "DQ13_50") (pintype "passive"))
    )
    (net (code "92") (name "/S_DB14") (class "Default")
      (node (ref "U1") (pin "139") (pinfunction "IO,_LVDS12p,_DQ1T7_139") (pintype "bidirectional"))
      (node (ref "U4") (pin "51") (pinfunction "DQ14_51") (pintype "passive"))
    )
    (net (code "93") (name "/S_DB15") (class "Default")
      (node (ref "U1") (pin "137") (pinfunction "IO,_LVDS12n,_DQ1T6_137") (pintype "bidirectional"))
      (node (ref "U4") (pin "53") (pinfunction "DQ15_53") (pintype "passive"))
    )
    (net (code "94") (name "/S_LDQM") (class "Default")
      (node (ref "U1") (pin "94") (pinfunction "IO,_LVDS34n,_DQ1R5_94") (pintype "bidirectional"))
      (node (ref "U4") (pin "15") (pinfunction "LDQM_15") (pintype "passive"))
    )
    (net (code "95") (name "/S_UDQM") (class "Default")
      (node (ref "U1") (pin "126") (pinfunction "IO,_LVDS21p,_DQ1T1_126") (pintype "bidirectional"))
      (node (ref "U4") (pin "39") (pinfunction "UDQM_39") (pintype "passive"))
    )
    (net (code "96") (name "/S_nCAS") (class "Default")
      (node (ref "U1") (pin "92") (pinfunction "IO,_LVDS35n,_DQ1R6_92") (pintype "bidirectional"))
      (node (ref "U4") (pin "17") (pinfunction "/CAS_17") (pintype "passive"))
    )
    (net (code "97") (name "/S_nCS") (class "Default")
      (node (ref "U1") (pin "86") (pinfunction "IO,_LVDS36n,_DQ1R7_86") (pintype "bidirectional"))
      (node (ref "U4") (pin "19") (pinfunction "/CS_19") (pintype "passive"))
    )
    (net (code "98") (name "/S_nRAS") (class "Default")
      (node (ref "U1") (pin "87") (pinfunction "IO,_LVDS36p,_(DPCLK6/DQS1R)_87") (pintype "bidirectional"))
      (node (ref "U4") (pin "18") (pinfunction "/RAS_18") (pintype "passive"))
    )
    (net (code "99") (name "/S_nWE") (class "Default")
      (node (ref "U1") (pin "93") (pinfunction "IO,_LVDS35p,_(DPCLK7/DQS0R)_93") (pintype "bidirectional"))
      (node (ref "U4") (pin "16") (pinfunction "/WE_16") (pintype "passive"))
    )
    (net (code "100") (name "/TCK") (class "Default")
      (node (ref "J3") (pin "1") (pinfunction "1_1") (pintype "passive"))
      (node (ref "R7") (pin "1") (pinfunction "1_1") (pintype "passive"))
      (node (ref "U1") (pin "12") (pinfunction "TCK_12") (pintype "input"))
    )
    (net (code "101") (name "/TDI") (class "Default")
      (node (ref "J3") (pin "9") (pinfunction "9_9") (pintype "passive"))
      (node (ref "R16") (pin "1") (pinfunction "1_1") (pintype "passive"))
      (node (ref "U1") (pin "13") (pinfunction "TDI_13") (pintype "input"))
    )
    (net (code "102") (name "/TDO") (class "Default")
      (node (ref "J3") (pin "3") (pinfunction "3_3") (pintype "passive"))
      (node (ref "R9") (pin "1") (pinfunction "1_1") (pintype "passive"))
      (node (ref "U1") (pin "10") (pinfunction "TDO_10") (pintype "output"))
    )
    (net (code "103") (name "/TMS") (class "Default")
      (node (ref "J3") (pin "5") (pinfunction "5_5") (pintype "passive"))
      (node (ref "R10") (pin "1") (pinfunction "1_1") (pintype "passive"))
      (node (ref "U1") (pin "11") (pinfunction "TMS_11") (pintype "input"))
    )
    (net (code "104") (name "/nCE") (class "Default")
      (node (ref "J2") (pin "6") (pinfunction "6_6") (pintype "passive"))
      (node (ref "R3") (pin "1") (pinfunction "1_1") (pintype "passive"))
      (node (ref "U1") (pin "16") (pinfunction "nCE_16") (pintype "input"))
    )
    (net (code "105") (name "/nCONFIG") (class "Default")
      (node (ref "J2") (pin "5") (pinfunction "5_5") (pintype "passive"))
      (node (ref "R5") (pin "1") (pinfunction "1_1") (pintype "passive"))
      (node (ref "U1") (pin "20") (pinfunction "nCONFIG_20") (pintype "input"))
    )
    (net (code "106") (name "/nCS") (class "Default")
      (node (ref "J2") (pin "8") (pinfunction "8_8") (pintype "passive"))
      (node (ref "U1") (pin "2") (pinfunction "IO,_(nCSO)_2") (pintype "bidirectional"))
      (node (ref "U5") (pin "1") (pinfunction "nCS_1") (pintype "input"))
    )
    (net (code "107") (name "/nSTATUS") (class "Default")
      (node (ref "R6") (pin "1") (pinfunction "1_1") (pintype "passive"))
      (node (ref "U1") (pin "82") (pinfunction "nSTATUS_82") (pintype "bidirectional"))
    )
    (net (code "108") (name "D1V2") (class "Default")
      (node (ref "C11") (pin "2") (pinfunction "2_2") (pintype "passive"))
      (node (ref "C12") (pin "2") (pinfunction "2_2") (pintype "passive"))
      (node (ref "C4") (pin "2") (pinfunction "2_2") (pintype "passive"))
      (node (ref "U1") (pin "107") (pinfunction "VCCD_PLL2_107") (pintype "power_in"))
      (node (ref "U1") (pin "109") (pinfunction "VCCA_PLL2_109") (pintype "power_in"))
      (node (ref "U1") (pin "124") (pinfunction "VCCINT_124") (pintype "power_in"))
      (node (ref "U1") (pin "131") (pinfunction "VCCINT_131") (pintype "power_in"))
      (node (ref "U1") (pin "35") (pinfunction "VCCD_PLL1_35") (pintype "power_in"))
      (node (ref "U1") (pin "37") (pinfunction "VCCA_PLL1_37") (pintype "power_in"))
      (node (ref "U1") (pin "50") (pinfunction "VCCINT_50") (pintype "power_in"))
      (node (ref "U1") (pin "62") (pinfunction "VCCINT_62") (pintype "power_in"))
      (node (ref "U3") (pin "5") (pinfunction "VOUT_5") (pintype "power_in"))
    )
    (net (code "109") (name "D3V3") (class "Default")
      (node (ref "C10") (pin "2") (pinfunction "2_2") (pintype "passive"))
      (node (ref "C13") (pin "2") (pinfunction "2_2") (pintype "passive"))
      (node (ref "C2") (pin "1") (pinfunction "1_1") (pintype "passive"))
      (node (ref "C3") (pin "2") (pinfunction "2_2") (pintype "passive"))
      (node (ref "C5") (pin "2") (pinfunction "2_2") (pintype "passive"))
      (node (ref "C6") (pin "2") (pinfunction "2_2") (pintype "passive"))
      (node (ref "C7") (pin "2") (pinfunction "2_2") (pintype "passive"))
      (node (ref "C8") (pin "2") (pinfunction "2_2") (pintype "passive"))
      (node (ref "C9") (pin "2") (pinfunction "2_2") (pintype "passive"))
      (node (ref "J2") (pin "4") (pinfunction "4_4") (pintype "passive"))
      (node (ref "J3") (pin "4") (pinfunction "4_4") (pintype "passive"))
      (node (ref "J3") (pin "6") (pinfunction "6_6") (pintype "passive"))
      (node (ref "L1") (pin "1") (pinfunction "A_1") (pintype "passive"))
      (node (ref "P2") (pin "27") (pinfunction "27_27") (pintype "passive"))
      (node (ref "Q1") (pin "1") (pinfunction "E_1") (pintype "passive"))
      (node (ref "Q2") (pin "1") (pinfunction "E_1") (pintype "passive"))
      (node (ref "Q3") (pin "1") (pinfunction "E_1") (pintype "passive"))
      (node (ref "Q4") (pin "1") (pinfunction "E_1") (pintype "passive"))
      (node (ref "R10") (pin "2") (pinfunction "2_2") (pintype "passive"))
      (node (ref "R11") (pin "1") (pinfunction "1_1") (pintype "passive"))
      (node (ref "R12") (pin "1") (pinfunction "1_1") (pintype "passive"))
      (node (ref "R13") (pin "1") (pinfunction "1_1") (pintype "passive"))
      (node (ref "R14") (pin "1") (pinfunction "1_1") (pintype "passive"))
      (node (ref "R15") (pin "1") (pinfunction "1_1") (pintype "passive"))
      (node (ref "R16") (pin "2") (pinfunction "2_2") (pintype "passive"))
      (node (ref "R2") (pin "2") (pinfunction "2_2") (pintype "passive"))
      (node (ref "R4") (pin "2") (pinfunction "2_2") (pintype "passive"))
      (node (ref "R5") (pin "2") (pinfunction "2_2") (pintype "passive"))
      (node (ref "R6") (pin "2") (pinfunction "2_2") (pintype "passive"))
      (node (ref "R9") (pin "2") (pinfunction "2_2") (pintype "passive"))
      (node (ref "U1") (pin "102") (pinfunction "VCCIO3_102") (pintype "power_in"))
      (node (ref "U1") (pin "116") (pinfunction "VCCIO2_116") (pintype "power_in"))
      (node (ref "U1") (pin "127") (pinfunction "VCCIO2_127") (pintype "power_in"))
      (node (ref "U1") (pin "138") (pinfunction "VCCIO2_138") (pintype "power_in"))
      (node (ref "U1") (pin "23") (pinfunction "VCCIO1_23") (pintype "power_in"))
      (node (ref "U1") (pin "29") (pinfunction "VCCIO1_29") (pintype "power_in"))
      (node (ref "U1") (pin "46") (pinfunction "VCCIO4_46") (pintype "power_in"))
      (node (ref "U1") (pin "5") (pinfunction "VCCIO1_5") (pintype "power_in"))
      (node (ref "U1") (pin "54") (pinfunction "VCCIO4_54") (pintype "power_in"))
      (node (ref "U1") (pin "66") (pinfunction "VCCIO4_66") (pintype "power_in"))
      (node (ref "U1") (pin "77") (pinfunction "VCCIO3_77") (pintype "power_in"))
      (node (ref "U1") (pin "95") (pinfunction "VCCIO3_95") (pintype "power_in"))
      (node (ref "U2") (pin "2") (pinfunction "OUT_2") (pintype "passive"))
      (node (ref "U3") (pin "1") (pinfunction "VIN_1") (pintype "passive"))
      (node (ref "U3") (pin "3") (pinfunction "EN_3") (pintype "power_in"))
      (node (ref "U4") (pin "1") (pinfunction "VDD_1") (pintype "power_in"))
      (node (ref "U4") (pin "14") (pinfunction "VDD_14") (pintype "power_in"))
      (node (ref "U4") (pin "27") (pinfunction "VDD_27") (pintype "power_in"))
      (node (ref "U4") (pin "3") (pinfunction "VDDQ_3") (pintype "power_in"))
      (node (ref "U4") (pin "43") (pinfunction "VDDQ_43") (pintype "power_in"))
      (node (ref "U4") (pin "49") (pinfunction "VDDQ_49") (pintype "power_in"))
      (node (ref "U4") (pin "9") (pinfunction "VDDQ_9") (pintype "power_in"))
      (node (ref "U5") (pin "3") (pinfunction "VCC_3") (pintype "power_in"))
      (node (ref "U5") (pin "7") (pinfunction "VCC_7") (pintype "power_in"))
      (node (ref "U5") (pin "8") (pinfunction "VCC_8") (pintype "power_in"))
      (node (ref "X1") (pin "4") (pinfunction "+_4") (pintype "passive"))
    )
    (net (code "110") (name "DGND") (class "Default")
      (node (ref "C1") (pin "2") (pinfunction "2_2") (pintype "passive"))
      (node (ref "C10") (pin "1") (pinfunction "1_1") (pintype "passive"))
      (node (ref "C11") (pin "1") (pinfunction "1_1") (pintype "passive"))
      (node (ref "C12") (pin "1") (pinfunction "1_1") (pintype "passive"))
      (node (ref "C13") (pin "1") (pinfunction "1_1") (pintype "passive"))
      (node (ref "C2") (pin "2") (pinfunction "2_2") (pintype "passive"))
      (node (ref "C3") (pin "1") (pinfunction "1_1") (pintype "passive"))
      (node (ref "C4") (pin "1") (pinfunction "1_1") (pintype "passive"))
      (node (ref "C5") (pin "1") (pinfunction "1_1") (pintype "passive"))
      (node (ref "C6") (pin "1") (pinfunction "1_1") (pintype "passive"))
      (node (ref "C7") (pin "1") (pinfunction "1_1") (pintype "passive"))
      (node (ref "C8") (pin "1") (pinfunction "1_1") (pintype "passive"))
      (node (ref "C9") (pin "1") (pinfunction "1_1") (pintype "passive"))
      (node (ref "J1") (pin "2") (pinfunction "2_2") (pintype "power_in"))
      (node (ref "J1") (pin "2A") (pinfunction "2A_2A") (pintype "power_in"))
      (node (ref "J1") (pin "2B") (pinfunction "2B_2B") (pintype "power_in"))
      (node (ref "J1") (pin "3") (pinfunction "3_3") (pintype "power_in"))
      (node (ref "J1") (pin "3A") (pinfunction "3A_3A") (pintype "power_in"))
      (node (ref "J1") (pin "3B") (pinfunction "3B_3B") (pintype "power_in"))
      (node (ref "J2") (pin "10") (pinfunction "10_10") (pintype "passive"))
      (node (ref "J2") (pin "2") (pinfunction "2_2") (pintype "passive"))
      (node (ref "J3") (pin "10") (pinfunction "10_10") (pintype "passive"))
      (node (ref "J3") (pin "2") (pinfunction "2_2") (pintype "passive"))
      (node (ref "L2") (pin "2") (pinfunction "K_2") (pintype "passive"))
      (node (ref "P1") (pin "10") (pinfunction "10_10") (pintype "passive"))
      (node (ref "P1") (pin "11") (pinfunction "11_11") (pintype "passive"))
      (node (ref "P1") (pin "12") (pinfunction "12_12") (pintype "passive"))
      (node (ref "P1") (pin "13") (pinfunction "13_13") (pintype "passive"))
      (node (ref "P1") (pin "14") (pinfunction "14_14") (pintype "passive"))
      (node (ref "P1") (pin "16") (pinfunction "16_16") (pintype "passive"))
      (node (ref "P1") (pin "18") (pinfunction "18_18") (pintype "passive"))
      (node (ref "P1") (pin "2") (pinfunction "2_2") (pintype "passive"))
      (node (ref "P1") (pin "20") (pinfunction "20_20") (pintype "passive"))
      (node (ref "P1") (pin "22") (pinfunction "22_22") (pintype "passive"))
      (node (ref "P1") (pin "4") (pinfunction "4_4") (pintype "passive"))
      (node (ref "P1") (pin "6") (pinfunction "6_6") (pintype "passive"))
      (node (ref "P1") (pin "8") (pinfunction "8_8") (pintype "passive"))
      (node (ref "P2") (pin "12") (pinfunction "12_12") (pintype "passive"))
      (node (ref "P2") (pin "14") (pinfunction "14_14") (pintype "passive"))
      (node (ref "P2") (pin "15") (pinfunction "15_15") (pintype "passive"))
      (node (ref "P2") (pin "16") (pinfunction "16_16") (pintype "passive"))
      (node (ref "P2") (pin "20") (pinfunction "20_20") (pintype "passive"))
      (node (ref "P2") (pin "24") (pinfunction "24_24") (pintype "passive"))
      (node (ref "P2") (pin "28") (pinfunction "28_28") (pintype "passive"))
      (node (ref "P2") (pin "4") (pinfunction "4_4") (pintype "passive"))
      (node (ref "P2") (pin "8") (pinfunction "8_8") (pintype "passive"))
      (node (ref "R1") (pin "1") (pinfunction "1_1") (pintype "passive"))
      (node (ref "R3") (pin "2") (pinfunction "2_2") (pintype "passive"))
      (node (ref "R7") (pin "2") (pinfunction "2_2") (pintype "passive"))
      (node (ref "S2") (pin "1") (pinfunction "COMMON_1") (pintype "passive"))
      (node (ref "S3") (pin "1") (pinfunction "COMMON_1") (pintype "passive"))
      (node (ref "S4") (pin "1") (pinfunction "COMMON_1") (pintype "passive"))
      (node (ref "S5") (pin "1") (pinfunction "COMMON_1") (pintype "passive"))
      (node (ref "S6") (pin "1") (pinfunction "COMMON_1") (pintype "passive"))
      (node (ref "U1") (pin "105") (pinfunction "GND_105") (pintype "power_in"))
      (node (ref "U1") (pin "106") (pinfunction "GND_PLL2_106") (pintype "power_in"))
      (node (ref "U1") (pin "108") (pinfunction "GND_PLL2_108") (pintype "power_in"))
      (node (ref "U1") (pin "110") (pinfunction "GNDA_PLL2_110") (pintype "power_in"))
      (node (ref "U1") (pin "111") (pinfunction "GND_111") (pintype "power_in"))
      (node (ref "U1") (pin "117") (pinfunction "GND_117") (pintype "power_in"))
      (node (ref "U1") (pin "123") (pinfunction "GND_123") (pintype "power_in"))
      (node (ref "U1") (pin "128") (pinfunction "GND_128") (pintype "power_in"))
      (node (ref "U1") (pin "130") (pinfunction "GND_130") (pintype "power_in"))
      (node (ref "U1") (pin "140") (pinfunction "GND_140") (pintype "power_in"))
      (node (ref "U1") (pin "18") (pinfunction "CLK1,_LVDSCLK0n_INPUT_18") (pintype "input"))
      (node (ref "U1") (pin "19") (pinfunction "GND_19") (pintype "power_in"))
      (node (ref "U1") (pin "21") (pinfunction "CLK2,_LVDSCLK1p_INPUT_21") (pintype "input"))
      (node (ref "U1") (pin "22") (pinfunction "CLK3,_LVDSCLK1n_INPUT_22") (pintype "input"))
      (node (ref "U1") (pin "33") (pinfunction "GND_33") (pintype "power_in"))
      (node (ref "U1") (pin "34") (pinfunction "GND_PLL1_34") (pintype "power_in"))
      (node (ref "U1") (pin "36") (pinfunction "GND_PLL1_36") (pintype "power_in"))
      (node (ref "U1") (pin "38") (pinfunction "GNDA_PLL1_38") (pintype "power_in"))
      (node (ref "U1") (pin "39") (pinfunction "GND_39") (pintype "power_in"))
      (node (ref "U1") (pin "49") (pinfunction "GND_49") (pintype "power_in"))
      (node (ref "U1") (pin "56") (pinfunction "GND_56") (pintype "power_in"))
      (node (ref "U1") (pin "6") (pinfunction "GND_6") (pintype "power_in"))
      (node (ref "U1") (pin "61") (pinfunction "GND_61") (pintype "power_in"))
      (node (ref "U1") (pin "68") (pinfunction "GND_68") (pintype "power_in"))
      (node (ref "U1") (pin "78") (pinfunction "GND_78") (pintype "power_in"))
      (node (ref "U1") (pin "84") (pinfunction "MSEL1_84") (pintype "input"))
      (node (ref "U1") (pin "85") (pinfunction "MSEL0_85") (pintype "input"))
      (node (ref "U1") (pin "98") (pinfunction "GND_98") (pintype "power_in"))
      (node (ref "U2") (pin "1") (pinfunction "A/G_1") (pintype "passive"))
      (node (ref "U3") (pin "2") (pinfunction "GND_2") (pintype "power_in"))
      (node (ref "U4") (pin "12") (pinfunction "GND_12") (pintype "power_in"))
      (node (ref "U4") (pin "28") (pinfunction "GND_28") (pintype "power_in"))
      (node (ref "U4") (pin "41") (pinfunction "GND_41") (pintype "power_in"))
      (node (ref "U4") (pin "46") (pinfunction "GND_46") (pintype "power_in"))
      (node (ref "U4") (pin "52") (pinfunction "GND_52") (pintype "power_in"))
      (node (ref "U4") (pin "54") (pinfunction "GND_54") (pintype "power_in"))
      (node (ref "U4") (pin "6") (pinfunction "GND_6") (pintype "power_in"))
      (node (ref "U5") (pin "4") (pinfunction "GND_4") (pintype "power_in"))
      (node (ref "X1") (pin "2") (pinfunction "-_2") (pintype "passive"))
    )
    (net (code "111") (name "Net-(J1-Pad1)") (class "Default")
      (node (ref "J1") (pin "1") (pinfunction "1_1") (pintype "power_in"))
      (node (ref "J1") (pin "1A") (pinfunction "1A_1A") (pintype "power_in"))
      (node (ref "J1") (pin "1B") (pinfunction "1B_1B") (pintype "power_in"))
      (node (ref "S1") (pin "4") (pinfunction "4_4") (pintype "passive"))
    )
    (net (code "112") (name "Net-(L1-K)") (class "Default")
      (node (ref "L1") (pin "2") (pinfunction "K_2") (pintype "passive"))
      (node (ref "R1") (pin "2") (pinfunction "2_2") (pintype "passive"))
    )
    (net (code "113") (name "Net-(L2-A)") (class "Default")
      (node (ref "L2") (pin "1") (pinfunction "A_1") (pintype "passive"))
      (node (ref "R19") (pin "2") (pinfunction "2_2") (pintype "passive"))
    )
    (net (code "114") (name "Net-(Q1-C)") (class "Default")
      (node (ref "DS1") (pin "1") (pinfunction "A_1") (pintype "passive"))
      (node (ref "DS1") (pin "6") (pinfunction "A_6") (pintype "passive"))
      (node (ref "Q1") (pin "3") (pinfunction "C_3") (pintype "passive"))
    )
    (net (code "115") (name "Net-(Q2-C)") (class "Default")
      (node (ref "DS2") (pin "1") (pinfunction "A_1") (pintype "passive"))
      (node (ref "DS2") (pin "6") (pinfunction "A_6") (pintype "passive"))
      (node (ref "Q2") (pin "3") (pinfunction "C_3") (pintype "passive"))
    )
    (net (code "116") (name "Net-(Q3-C)") (class "Default")
      (node (ref "DS3") (pin "1") (pinfunction "A_1") (pintype "passive"))
      (node (ref "DS3") (pin "6") (pinfunction "A_6") (pintype "passive"))
      (node (ref "Q3") (pin "3") (pinfunction "C_3") (pintype "passive"))
    )
    (net (code "117") (name "Net-(Q4-C)") (class "Default")
      (node (ref "DS4") (pin "1") (pinfunction "A_1") (pintype "passive"))
      (node (ref "DS4") (pin "6") (pinfunction "A_6") (pintype "passive"))
      (node (ref "Q4") (pin "3") (pinfunction "C_3") (pintype "passive"))
    )
    (net (code "118") (name "Net-(S2-NO)") (class "Default")
      (node (ref "R11") (pin "2") (pinfunction "2_2") (pintype "passive"))
      (node (ref "R17") (pin "2") (pinfunction "2_2") (pintype "passive"))
      (node (ref "S2") (pin "2") (pinfunction "NO_2") (pintype "passive"))
    )
    (net (code "119") (name "Net-(S3-NO)") (class "Default")
      (node (ref "R12") (pin "2") (pinfunction "2_2") (pintype "passive"))
      (node (ref "R18") (pin "2") (pinfunction "2_2") (pintype "passive"))
      (node (ref "S3") (pin "2") (pinfunction "NO_2") (pintype "passive"))
    )
    (net (code "120") (name "Net-(S4-NO)") (class "Default")
      (node (ref "R13") (pin "2") (pinfunction "2_2") (pintype "passive"))
      (node (ref "R20") (pin "2") (pinfunction "2_2") (pintype "passive"))
      (node (ref "S4") (pin "2") (pinfunction "NO_2") (pintype "passive"))
    )
    (net (code "121") (name "Net-(S5-NO)") (class "Default")
      (node (ref "R14") (pin "2") (pinfunction "2_2") (pintype "passive"))
      (node (ref "R21") (pin "2") (pinfunction "2_2") (pintype "passive"))
      (node (ref "S5") (pin "2") (pinfunction "NO_2") (pintype "passive"))
    )
    (net (code "122") (name "Net-(S6-NO)") (class "Default")
      (node (ref "R15") (pin "2") (pinfunction "2_2") (pintype "passive"))
      (node (ref "R22") (pin "2") (pinfunction "2_2") (pintype "passive"))
      (node (ref "S6") (pin "2") (pinfunction "NO_2") (pintype "passive"))
    )
    (net (code "123") (name "Net-(U1I-CLK0,_LVDSCLK0p_INPUT)") (class "Default")
      (node (ref "R8") (pin "1") (pinfunction "1_1") (pintype "passive"))
      (node (ref "U1") (pin "17") (pinfunction "CLK0,_LVDSCLK0p_INPUT_17") (pintype "input"))
    )
    (net (code "124") (name "Net-(U2-IN)") (class "Default")
      (node (ref "C1") (pin "1") (pinfunction "1_1") (pintype "passive"))
      (node (ref "S1") (pin "5") (pinfunction "5_5") (pintype "passive"))
      (node (ref "U2") (pin "3") (pinfunction "IN_3") (pintype "passive"))
    )
    (net (code "125") (name "Net-(X1-~)") (class "Default")
      (node (ref "R8") (pin "2") (pinfunction "2_2") (pintype "passive"))
      (node (ref "X1") (pin "3") (pinfunction "~_3") (pintype "passive"))
    )
    (net (code "126") (name "unconnected-(J3-Pad7)") (class "Default")
      (node (ref "J3") (pin "7") (pinfunction "7_7") (pintype "passive+no_connect"))
    )
    (net (code "127") (name "unconnected-(J3-Pad8)") (class "Default")
      (node (ref "J3") (pin "8") (pinfunction "8_8") (pintype "passive+no_connect"))
    )
    (net (code "128") (name "unconnected-(S1-Pad1)") (class "Default")
      (node (ref "S1") (pin "1") (pinfunction "1_1") (pintype "passive"))
    )
    (net (code "129") (name "unconnected-(S1-Pad2)") (class "Default")
      (node (ref "S1") (pin "2") (pinfunction "2_2") (pintype "passive"))
    )
    (net (code "130") (name "unconnected-(S1-Pad3)") (class "Default")
      (node (ref "S1") (pin "3") (pinfunction "3_3") (pintype "passive"))
    )
    (net (code "131") (name "unconnected-(S1-Pad6)") (class "Default")
      (node (ref "S1") (pin "6") (pinfunction "6_6") (pintype "passive"))
    )
    (net (code "132") (name "unconnected-(U3-ADJ{slash}BYP-Pad4)") (class "Default")
      (node (ref "U3") (pin "4") (pinfunction "ADJ/BYP_4") (pintype "power_in+no_connect"))
    )
    (net (code "133") (name "unconnected-(U4-NC-Pad36)") (class "Default")
      (node (ref "U4") (pin "36") (pinfunction "NC_36") (pintype "passive+no_connect"))
    )
    (net (code "134") (name "unconnected-(U4-NC-Pad40)") (class "Default")
      (node (ref "U4") (pin "40") (pinfunction "NC_40") (pintype "passive+no_connect"))
    )
    (net (code "135") (name "unconnected-(X1-N-Pad1)") (class "Default")
      (node (ref "X1") (pin "1") (pinfunction "N_1") (pintype "passive+no_connect"))
    )
  )
)
